# 4_FPGA.net
KiCad netlist of a schematic drawn in Altium Designer
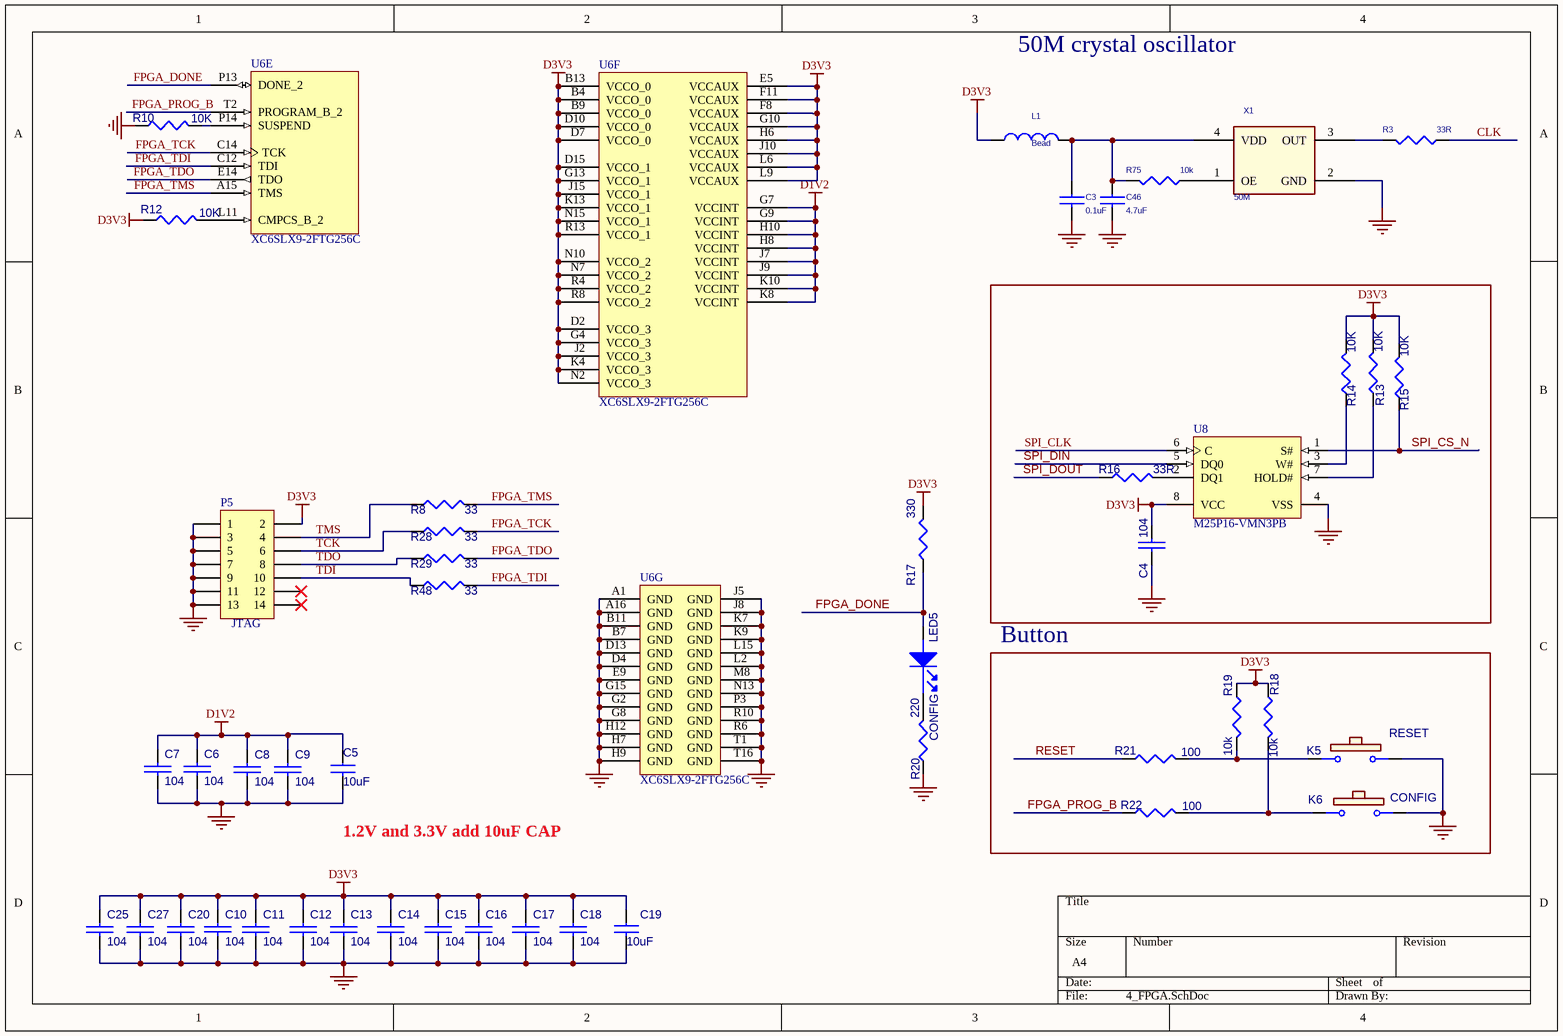
[diagram p0: 4_FPGA.SchDoc]

(export (version "E")
  (design (tool "Eeschema 10.0.6"))
  (components
    (comp (ref "C3") (value "0.1uF") (libsource (lib "*") (part "CAP NP_Dup2")))
    (comp (ref "C4") (value "104") (libsource (lib "*") (part "C_Dup4")))
    (comp (ref "C5") (value "10uF") (libsource (lib "*") (part "CAP NP_Dup2")))
    (comp (ref "C6") (value "104") (libsource (lib "*") (part "C_Dup4")))
    (comp (ref "C7") (value "104") (libsource (lib "*") (part "C_Dup4")))
    (comp (ref "C8") (value "104") (libsource (lib "*") (part "C_Dup4")))
    (comp (ref "C9") (value "104") (libsource (lib "*") (part "C_Dup4")))
    (comp (ref "C10") (value "104") (libsource (lib "*") (part "C_Dup4")))
    (comp (ref "C11") (value "104") (libsource (lib "*") (part "C_Dup4")))
    (comp (ref "C12") (value "104") (libsource (lib "*") (part "C_Dup4")))
    (comp (ref "C13") (value "104") (libsource (lib "*") (part "C_Dup4")))
    (comp (ref "C14") (value "104") (libsource (lib "*") (part "C_Dup4")))
    (comp (ref "C15") (value "104") (libsource (lib "*") (part "C_Dup4")))
    (comp (ref "C16") (value "104") (libsource (lib "*") (part "C_Dup4")))
    (comp (ref "C17") (value "104") (libsource (lib "*") (part "C_Dup4")))
    (comp (ref "C18") (value "104") (libsource (lib "*") (part "C_Dup4")))
    (comp (ref "C19") (value "10uF") (libsource (lib "*") (part "CAP NP_Dup2")))
    (comp (ref "C20") (value "104") (libsource (lib "*") (part "C_Dup4")))
    (comp (ref "C25") (value "104") (libsource (lib "*") (part "C_Dup4")))
    (comp (ref "C27") (value "104") (libsource (lib "*") (part "C_Dup4")))
    (comp (ref "C46") (value "4.7uF") (libsource (lib "*") (part "CAP NP_Dup2")))
    (comp (ref "K5") (value "RESET") (footprint "KEY735SO") (libsource (lib "*") (part "KEYB")))
    (comp (ref "K6") (value "CONFIG") (footprint "KEY735SO") (libsource (lib "") (part "KEYB_1")))
    (comp (ref "L1") (value "Bead") (libsource (lib "*") (part "INDUCTOR")))
    (comp (ref "LED5") (value "CONFIG") (footprint "LEDSO") (libsource (lib "*") (part "LED_Dup1")))
    (comp (ref "P5")
      (value "JTAG")
      (footprint "JTAG14-.5")
      (description "Header, 7-Pin, Dual row")
      (fields (field (name "PUBLISHER") "Altium Limited"))
      (libsource (lib "Miscellaneous Connectors") (part "Header 7X2"))
    )
    (comp (ref "R3") (value "33R") (libsource (lib "*") (part "RESISTOR")))
    (comp (ref "R8") (value "33") (libsource (lib "DB4-15") (part "R")))
    (comp (ref "R10") (value "10K") (libsource (lib "DB4-15") (part "R")))
    (comp (ref "R12") (value "10K") (libsource (lib "DB4-15") (part "R")))
    (comp (ref "R13") (value "10K") (libsource (lib "DB4-15") (part "R")))
    (comp (ref "R14") (value "10K") (libsource (lib "DB4-15") (part "R")))
    (comp (ref "R15") (value "10K") (libsource (lib "DB4-15") (part "R")))
    (comp (ref "R16") (value "33R") (footprint "0603") (libsource (lib "*") (part "R_Dup3")))
    (comp (ref "R17") (value "330") (footprint "0603") (libsource (lib "*") (part "R_Dup1")))
    (comp (ref "R18") (value "10k") (footprint "0603") (libsource (lib "*") (part "R_Dup2")))
    (comp (ref "R19") (value "10k") (footprint "0603") (libsource (lib "*") (part "R_Dup2")))
    (comp (ref "R20") (value "220") (footprint "0603") (libsource (lib "*") (part "R_Dup1")))
    (comp (ref "R21") (value "100") (footprint "0603") (libsource (lib "*") (part "R_Dup2")))
    (comp (ref "R22") (value "100") (footprint "0603") (libsource (lib "*") (part "R_Dup2")))
    (comp (ref "R28") (value "33") (libsource (lib "DB4-15") (part "R")))
    (comp (ref "R29") (value "33") (libsource (lib "DB4-15") (part "R")))
    (comp (ref "R48") (value "33") (libsource (lib "DB4-15") (part "R")))
    (comp (ref "R75") (value "10k") (libsource (lib "*") (part "RESISTOR")))
    (comp (ref "U6")
      (value "XC6SLX9-2FTG256C")
      (footprint "FTG256")
      (libsource (lib "Xilinx Spartan-6") (part "XC6SLX9-2FTG256C"))
    )
    (comp (ref "U8")
      (value "M25P16-VMN3PB")
      (footprint "SO8")
      (description "16 Mb (x1) Automotive Serial NOR Flash Memory, 75 MHz, 2.7 to 3.6 V, 8-pin SO8 Narrow (MN), Tube")
      (fields (field (name "VOLTAGE") "2.7V-3.6V爘ISHIDDEN=T") (field (name "MANUFACTURER") "Micron"))
      (libsource (lib "Micron Memory Serial NOR Flash") (part "M25P16-VMN3PB"))
    )
    (comp (ref "X1") (value "50M") (libsource (lib "*") (part "OSC")))
  )
  (nets
    (net (code "1") (name "/CLK") (class "Default")
      (node (ref "R3") (pin "1") (pinfunction "1_1") (pintype "passive"))
    )
    (net (code "2") (name "/FPGA_DONE") (class "Default")
      (node (ref "LED5") (pin "1") (pinfunction "ANODE_1") (pintype "passive"))
      (node (ref "R17") (pin "1") (pinfunction "1_1") (pintype "passive"))
      (node (ref "U6") (pin "P13") (pinfunction "DONE_2_P13") (pintype "bidirectional"))
    )
    (net (code "3") (name "/FPGA_PROG_B") (class "Default")
      (node (ref "R22") (pin "1") (pinfunction "1_1") (pintype "passive"))
      (node (ref "U6") (pin "T2") (pinfunction "PROGRAM_B_2_T2") (pintype "input"))
    )
    (net (code "4") (name "/FPGA_TCK") (class "Default")
      (node (ref "R28") (pin "2") (pinfunction "2_2") (pintype "passive"))
      (node (ref "U6") (pin "C14") (pinfunction "TCK_C14") (pintype "input"))
    )
    (net (code "5") (name "/FPGA_TDI") (class "Default")
      (node (ref "R48") (pin "2") (pinfunction "2_2") (pintype "passive"))
      (node (ref "U6") (pin "C12") (pinfunction "TDI_C12") (pintype "input"))
    )
    (net (code "6") (name "/FPGA_TDO") (class "Default")
      (node (ref "R29") (pin "2") (pinfunction "2_2") (pintype "passive"))
      (node (ref "U6") (pin "E14") (pinfunction "TDO_E14") (pintype "output"))
    )
    (net (code "7") (name "/FPGA_TMS") (class "Default")
      (node (ref "R8") (pin "2") (pinfunction "2_2") (pintype "passive"))
      (node (ref "U6") (pin "A15") (pinfunction "TMS_A15") (pintype "input"))
    )
    (net (code "8") (name "/RESET") (class "Default")
      (node (ref "R21") (pin "1") (pinfunction "1_1") (pintype "passive"))
    )
    (net (code "9") (name "/SPI_CLK") (class "Default")
      (node (ref "U8") (pin "6") (pinfunction "C_6") (pintype "input"))
    )
    (net (code "10") (name "/SPI_CS_N") (class "Default")
      (node (ref "R15") (pin "1") (pinfunction "1_1") (pintype "passive"))
      (node (ref "U8") (pin "1") (pinfunction "S#_1") (pintype "input"))
    )
    (net (code "11") (name "/SPI_DIN") (class "Default")
      (node (ref "U8") (pin "5") (pinfunction "DQ0_5") (pintype "input"))
    )
    (net (code "12") (name "/SPI_DOUT") (class "Default")
      (node (ref "R16") (pin "1") (pinfunction "1_1") (pintype "passive"))
    )
    (net (code "13") (name "/TCK") (class "Default")
      (node (ref "P5") (pin "6") (pinfunction "6_6") (pintype "passive"))
      (node (ref "R28") (pin "1") (pinfunction "1_1") (pintype "passive"))
    )
    (net (code "14") (name "/TDI") (class "Default")
      (node (ref "P5") (pin "10") (pinfunction "10_10") (pintype "passive"))
      (node (ref "R48") (pin "1") (pinfunction "1_1") (pintype "passive"))
    )
    (net (code "15") (name "/TDO") (class "Default")
      (node (ref "P5") (pin "8") (pinfunction "8_8") (pintype "passive"))
      (node (ref "R29") (pin "1") (pinfunction "1_1") (pintype "passive"))
    )
    (net (code "16") (name "/TMS") (class "Default")
      (node (ref "P5") (pin "4") (pinfunction "4_4") (pintype "passive"))
      (node (ref "R8") (pin "1") (pinfunction "1_1") (pintype "passive"))
    )
    (net (code "17") (name "D1V2") (class "Default")
      (node (ref "C5") (pin "1") (pinfunction "1_1") (pintype "passive"))
      (node (ref "C6") (pin "1") (pinfunction "1_1") (pintype "passive"))
      (node (ref "C7") (pin "1") (pinfunction "1_1") (pintype "passive"))
      (node (ref "C8") (pin "1") (pinfunction "1_1") (pintype "passive"))
      (node (ref "C9") (pin "1") (pinfunction "1_1") (pintype "passive"))
      (node (ref "U6") (pin "G7") (pinfunction "VCCINT_G7") (pintype "power_in"))
      (node (ref "U6") (pin "G9") (pinfunction "VCCINT_G9") (pintype "power_in"))
      (node (ref "U6") (pin "H10") (pinfunction "VCCINT_H10") (pintype "power_in"))
      (node (ref "U6") (pin "H8") (pinfunction "VCCINT_H8") (pintype "power_in"))
      (node (ref "U6") (pin "J7") (pinfunction "VCCINT_J7") (pintype "power_in"))
      (node (ref "U6") (pin "J9") (pinfunction "VCCINT_J9") (pintype "power_in"))
      (node (ref "U6") (pin "K10") (pinfunction "VCCINT_K10") (pintype "power_in"))
      (node (ref "U6") (pin "K8") (pinfunction "VCCINT_K8") (pintype "power_in"))
    )
    (net (code "18") (name "D3V3") (class "Default")
      (node (ref "C10") (pin "1") (pinfunction "1_1") (pintype "passive"))
      (node (ref "C11") (pin "1") (pinfunction "1_1") (pintype "passive"))
      (node (ref "C12") (pin "1") (pinfunction "1_1") (pintype "passive"))
      (node (ref "C13") (pin "1") (pinfunction "1_1") (pintype "passive"))
      (node (ref "C14") (pin "1") (pinfunction "1_1") (pintype "passive"))
      (node (ref "C15") (pin "1") (pinfunction "1_1") (pintype "passive"))
      (node (ref "C16") (pin "1") (pinfunction "1_1") (pintype "passive"))
      (node (ref "C17") (pin "1") (pinfunction "1_1") (pintype "passive"))
      (node (ref "C18") (pin "1") (pinfunction "1_1") (pintype "passive"))
      (node (ref "C19") (pin "1") (pinfunction "1_1") (pintype "passive"))
      (node (ref "C20") (pin "1") (pinfunction "1_1") (pintype "passive"))
      (node (ref "C25") (pin "1") (pinfunction "1_1") (pintype "passive"))
      (node (ref "C27") (pin "1") (pinfunction "1_1") (pintype "passive"))
      (node (ref "C4") (pin "2") (pinfunction "2_2") (pintype "passive"))
      (node (ref "L1") (pin "1") (pinfunction "1_1") (pintype "passive"))
      (node (ref "P5") (pin "2") (pinfunction "2_2") (pintype "passive"))
      (node (ref "R12") (pin "1") (pinfunction "1_1") (pintype "passive"))
      (node (ref "R13") (pin "2") (pinfunction "2_2") (pintype "passive"))
      (node (ref "R14") (pin "2") (pinfunction "2_2") (pintype "passive"))
      (node (ref "R15") (pin "2") (pinfunction "2_2") (pintype "passive"))
      (node (ref "R17") (pin "2") (pinfunction "2_2") (pintype "passive"))
      (node (ref "R18") (pin "1") (pinfunction "1_1") (pintype "passive"))
      (node (ref "R19") (pin "1") (pinfunction "1_1") (pintype "passive"))
      (node (ref "U6") (pin "B13") (pinfunction "VCCO_0_B13") (pintype "power_in"))
      (node (ref "U6") (pin "B4") (pinfunction "VCCO_0_B4") (pintype "power_in"))
      (node (ref "U6") (pin "B9") (pinfunction "VCCO_0_B9") (pintype "power_in"))
      (node (ref "U6") (pin "D10") (pinfunction "VCCO_0_D10") (pintype "power_in"))
      (node (ref "U6") (pin "D15") (pinfunction "VCCO_1_D15") (pintype "power_in"))
      (node (ref "U6") (pin "D2") (pinfunction "VCCO_3_D2") (pintype "power_in"))
      (node (ref "U6") (pin "D7") (pinfunction "VCCO_0_D7") (pintype "power_in"))
      (node (ref "U6") (pin "E5") (pinfunction "VCCAUX_E5") (pintype "power_in"))
      (node (ref "U6") (pin "F11") (pinfunction "VCCAUX_F11") (pintype "power_in"))
      (node (ref "U6") (pin "F8") (pinfunction "VCCAUX_F8") (pintype "power_in"))
      (node (ref "U6") (pin "G10") (pinfunction "VCCAUX_G10") (pintype "power_in"))
      (node (ref "U6") (pin "G13") (pinfunction "VCCO_1_G13") (pintype "power_in"))
      (node (ref "U6") (pin "G4") (pinfunction "VCCO_3_G4") (pintype "power_in"))
      (node (ref "U6") (pin "H6") (pinfunction "VCCAUX_H6") (pintype "power_in"))
      (node (ref "U6") (pin "J10") (pinfunction "VCCAUX_J10") (pintype "power_in"))
      (node (ref "U6") (pin "J15") (pinfunction "VCCO_1_J15") (pintype "power_in"))
      (node (ref "U6") (pin "J2") (pinfunction "VCCO_3_J2") (pintype "power_in"))
      (node (ref "U6") (pin "K13") (pinfunction "VCCO_1_K13") (pintype "power_in"))
      (node (ref "U6") (pin "K4") (pinfunction "VCCO_3_K4") (pintype "power_in"))
      (node (ref "U6") (pin "L6") (pinfunction "VCCAUX_L6") (pintype "power_in"))
      (node (ref "U6") (pin "L9") (pinfunction "VCCAUX_L9") (pintype "power_in"))
      (node (ref "U6") (pin "N10") (pinfunction "VCCO_2_N10") (pintype "power_in"))
      (node (ref "U6") (pin "N15") (pinfunction "VCCO_1_N15") (pintype "power_in"))
      (node (ref "U6") (pin "N2") (pinfunction "VCCO_3_N2") (pintype "power_in"))
      (node (ref "U6") (pin "N7") (pinfunction "VCCO_2_N7") (pintype "power_in"))
      (node (ref "U6") (pin "R13") (pinfunction "VCCO_1_R13") (pintype "power_in"))
      (node (ref "U6") (pin "R4") (pinfunction "VCCO_2_R4") (pintype "power_in"))
      (node (ref "U6") (pin "R8") (pinfunction "VCCO_2_R8") (pintype "power_in"))
      (node (ref "U8") (pin "8") (pinfunction "VCC_8") (pintype "power_in"))
    )
    (net (code "19") (name "GND") (class "Default")
      (node (ref "C10") (pin "2") (pinfunction "2_2") (pintype "passive"))
      (node (ref "C11") (pin "2") (pinfunction "2_2") (pintype "passive"))
      (node (ref "C12") (pin "2") (pinfunction "2_2") (pintype "passive"))
      (node (ref "C13") (pin "2") (pinfunction "2_2") (pintype "passive"))
      (node (ref "C14") (pin "2") (pinfunction "2_2") (pintype "passive"))
      (node (ref "C15") (pin "2") (pinfunction "2_2") (pintype "passive"))
      (node (ref "C16") (pin "2") (pinfunction "2_2") (pintype "passive"))
      (node (ref "C17") (pin "2") (pinfunction "2_2") (pintype "passive"))
      (node (ref "C18") (pin "2") (pinfunction "2_2") (pintype "passive"))
      (node (ref "C19") (pin "2") (pinfunction "2_2") (pintype "passive"))
      (node (ref "C20") (pin "2") (pinfunction "2_2") (pintype "passive"))
      (node (ref "C25") (pin "2") (pinfunction "2_2") (pintype "passive"))
      (node (ref "C27") (pin "2") (pinfunction "2_2") (pintype "passive"))
      (node (ref "C3") (pin "2") (pinfunction "2_2") (pintype "passive"))
      (node (ref "C4") (pin "1") (pinfunction "1_1") (pintype "passive"))
      (node (ref "C46") (pin "2") (pinfunction "2_2") (pintype "passive"))
      (node (ref "C5") (pin "2") (pinfunction "2_2") (pintype "passive"))
      (node (ref "C6") (pin "2") (pinfunction "2_2") (pintype "passive"))
      (node (ref "C7") (pin "2") (pinfunction "2_2") (pintype "passive"))
      (node (ref "C8") (pin "2") (pinfunction "2_2") (pintype "passive"))
      (node (ref "C9") (pin "2") (pinfunction "2_2") (pintype "passive"))
      (node (ref "K5") (pin "2") (pinfunction "2_2") (pintype "passive"))
      (node (ref "K6") (pin "1") (pinfunction "1_1") (pintype "passive"))
      (node (ref "P5") (pin "1") (pinfunction "1_1") (pintype "passive"))
      (node (ref "P5") (pin "11") (pinfunction "11_11") (pintype "passive"))
      (node (ref "P5") (pin "13") (pinfunction "13_13") (pintype "passive"))
      (node (ref "P5") (pin "3") (pinfunction "3_3") (pintype "passive"))
      (node (ref "P5") (pin "5") (pinfunction "5_5") (pintype "passive"))
      (node (ref "P5") (pin "7") (pinfunction "7_7") (pintype "passive"))
      (node (ref "P5") (pin "9") (pinfunction "9_9") (pintype "passive"))
      (node (ref "R10") (pin "1") (pinfunction "1_1") (pintype "passive"))
      (node (ref "R20") (pin "1") (pinfunction "1_1") (pintype "passive"))
      (node (ref "U6") (pin "A1") (pinfunction "GND_A1") (pintype "power_in"))
      (node (ref "U6") (pin "A16") (pinfunction "GND_A16") (pintype "power_in"))
      (node (ref "U6") (pin "B11") (pinfunction "GND_B11") (pintype "power_in"))
      (node (ref "U6") (pin "B7") (pinfunction "GND_B7") (pintype "power_in"))
      (node (ref "U6") (pin "D13") (pinfunction "GND_D13") (pintype "power_in"))
      (node (ref "U6") (pin "D4") (pinfunction "GND_D4") (pintype "power_in"))
      (node (ref "U6") (pin "E9") (pinfunction "GND_E9") (pintype "power_in"))
      (node (ref "U6") (pin "G15") (pinfunction "GND_G15") (pintype "power_in"))
      (node (ref "U6") (pin "G2") (pinfunction "GND_G2") (pintype "power_in"))
      (node (ref "U6") (pin "G8") (pinfunction "GND_G8") (pintype "power_in"))
      (node (ref "U6") (pin "H12") (pinfunction "GND_H12") (pintype "power_in"))
      (node (ref "U6") (pin "H7") (pinfunction "GND_H7") (pintype "power_in"))
      (node (ref "U6") (pin "H9") (pinfunction "GND_H9") (pintype "power_in"))
      (node (ref "U6") (pin "J5") (pinfunction "GND_J5") (pintype "power_in"))
      (node (ref "U6") (pin "J8") (pinfunction "GND_J8") (pintype "power_in"))
      (node (ref "U6") (pin "K7") (pinfunction "GND_K7") (pintype "power_in"))
      (node (ref "U6") (pin "K9") (pinfunction "GND_K9") (pintype "power_in"))
      (node (ref "U6") (pin "L15") (pinfunction "GND_L15") (pintype "power_in"))
      (node (ref "U6") (pin "L2") (pinfunction "GND_L2") (pintype "power_in"))
      (node (ref "U6") (pin "M8") (pinfunction "GND_M8") (pintype "power_in"))
      (node (ref "U6") (pin "N13") (pinfunction "GND_N13") (pintype "power_in"))
      (node (ref "U6") (pin "P3") (pinfunction "GND_P3") (pintype "power_in"))
      (node (ref "U6") (pin "R10") (pinfunction "GND_R10") (pintype "power_in"))
      (node (ref "U6") (pin "R6") (pinfunction "GND_R6") (pintype "power_in"))
      (node (ref "U6") (pin "T1") (pinfunction "GND_T1") (pintype "power_in"))
      (node (ref "U6") (pin "T16") (pinfunction "GND_T16") (pintype "power_in"))
      (node (ref "U8") (pin "4") (pinfunction "VSS_4") (pintype "power_in"))
      (node (ref "X1") (pin "2") (pinfunction "GND_2") (pintype "passive"))
    )
    (net (code "20") (name "Net-(K5-Pad1)") (class "Default")
      (node (ref "K5") (pin "1") (pinfunction "1_1") (pintype "passive"))
      (node (ref "R19") (pin "2") (pinfunction "2_2") (pintype "passive"))
      (node (ref "R21") (pin "2") (pinfunction "2_2") (pintype "passive"))
    )
    (net (code "21") (name "Net-(K6-Pad2)") (class "Default")
      (node (ref "K6") (pin "2") (pinfunction "2_2") (pintype "passive"))
      (node (ref "R18") (pin "2") (pinfunction "2_2") (pintype "passive"))
      (node (ref "R22") (pin "2") (pinfunction "2_2") (pintype "passive"))
    )
    (net (code "22") (name "Net-(LED5-CATHODE)") (class "Default")
      (node (ref "LED5") (pin "2") (pinfunction "CATHODE_2") (pintype "passive"))
      (node (ref "R20") (pin "2") (pinfunction "2_2") (pintype "passive"))
    )
    (net (code "23") (name "Net-(U6E-CMPCS_B_2)") (class "Default")
      (node (ref "R12") (pin "2") (pinfunction "2_2") (pintype "passive"))
      (node (ref "U6") (pin "L11") (pinfunction "CMPCS_B_2_L11") (pintype "input"))
    )
    (net (code "24") (name "Net-(U6E-SUSPEND)") (class "Default")
      (node (ref "R10") (pin "2") (pinfunction "2_2") (pintype "passive"))
      (node (ref "U6") (pin "P14") (pinfunction "SUSPEND_P14") (pintype "input"))
    )
    (net (code "25") (name "Net-(U8-DQ1)") (class "Default")
      (node (ref "R16") (pin "2") (pinfunction "2_2") (pintype "passive"))
      (node (ref "U8") (pin "2") (pinfunction "DQ1_2") (pintype "tri_state"))
    )
    (net (code "26") (name "Net-(U8-HOLD#)") (class "Default")
      (node (ref "R13") (pin "1") (pinfunction "1_1") (pintype "passive"))
      (node (ref "U8") (pin "7") (pinfunction "HOLD#_7") (pintype "input"))
    )
    (net (code "27") (name "Net-(U8-W#)") (class "Default")
      (node (ref "R14") (pin "1") (pinfunction "1_1") (pintype "passive"))
      (node (ref "U8") (pin "3") (pinfunction "W#_3") (pintype "input"))
    )
    (net (code "28") (name "Net-(X1-OE)") (class "Default")
      (node (ref "R75") (pin "1") (pinfunction "1_1") (pintype "passive"))
      (node (ref "X1") (pin "1") (pinfunction "OE_1") (pintype "passive"))
    )
    (net (code "29") (name "Net-(X1-OUT)") (class "Default")
      (node (ref "R3") (pin "2") (pinfunction "2_2") (pintype "passive"))
      (node (ref "X1") (pin "3") (pinfunction "OUT_3") (pintype "passive"))
    )
    (net (code "30") (name "Net-(X1-VDD)") (class "Default")
      (node (ref "C3") (pin "1") (pinfunction "1_1") (pintype "passive"))
      (node (ref "C46") (pin "1") (pinfunction "1_1") (pintype "passive"))
      (node (ref "L1") (pin "2") (pinfunction "2_2") (pintype "passive"))
      (node (ref "R75") (pin "2") (pinfunction "2_2") (pintype "passive"))
      (node (ref "X1") (pin "4") (pinfunction "VDD_4") (pintype "passive"))
    )
    (net (code "31") (name "unconnected-(P5-Pad12)") (class "Default")
      (node (ref "P5") (pin "12") (pinfunction "12_12") (pintype "passive+no_connect"))
    )
    (net (code "32") (name "unconnected-(P5-Pad14)") (class "Default")
      (node (ref "P5") (pin "14") (pinfunction "14_14") (pintype "passive+no_connect"))
    )
  )
)
